# Z80fun_CPUtest.net
KiCad netlist of a schematic drawn in EAGLE
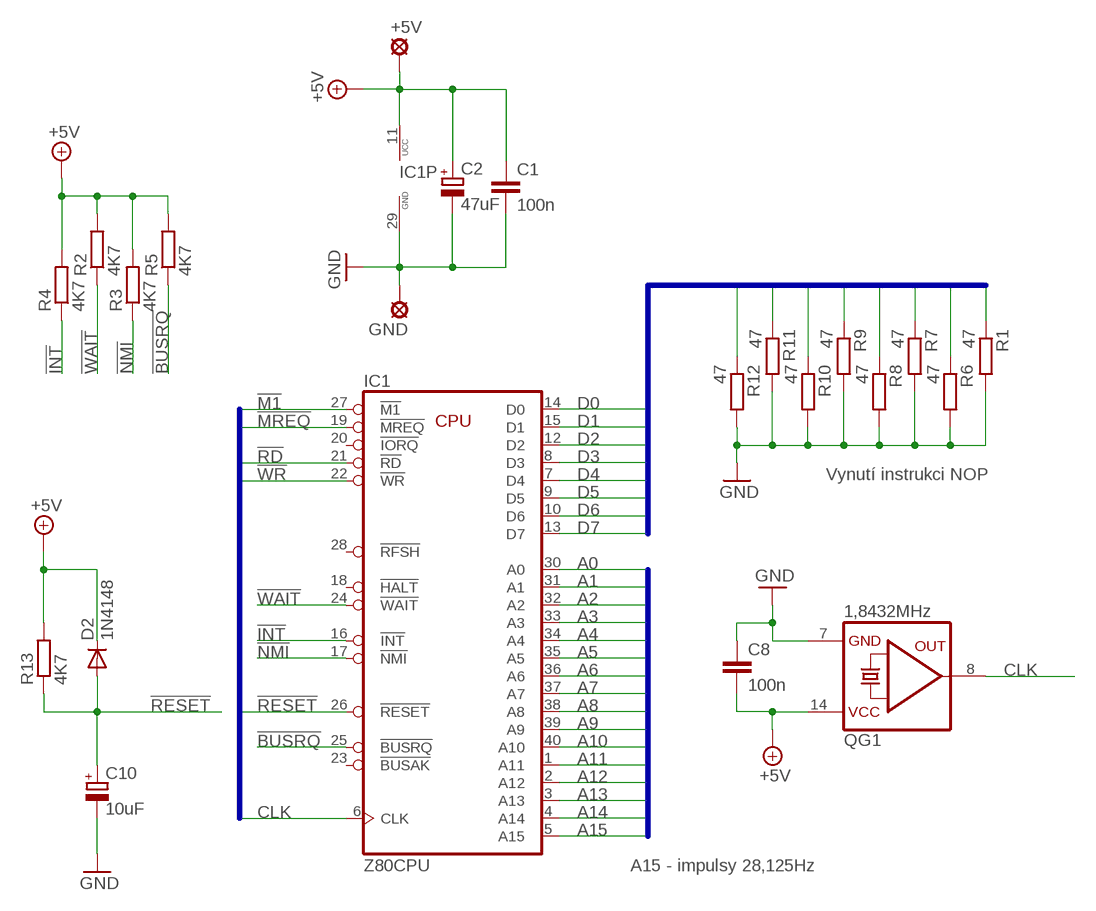
[diagram p0: schematic, sheet 1]

(export (version "E")
  (design (tool "Eeschema 10.0.6"))
  (components
    (comp (ref "+5V")
      (value "LSP11")
      (footprint "eagle-import:LSP11")
      (libsource (lib "eagle-import") (part "LSP11"))
    )
    (comp (ref "C1")
      (value "100n")
      (footprint "eagle-import:C050-024X044")
      (libsource (lib "eagle-import") (part "C-EU050-024X044"))
    )
    (comp (ref "C2")
      (value "47uF")
      (footprint "eagle-import:E2,5-6E")
      (libsource (lib "eagle-import") (part "CPOL-EUE2,5-6E"))
    )
    (comp (ref "C8")
      (value "100n")
      (footprint "eagle-import:C050-024X044")
      (libsource (lib "eagle-import") (part "C-EU050-024X044"))
    )
    (comp (ref "C10")
      (value "10uF")
      (footprint "eagle-import:E2,5-5")
      (libsource (lib "eagle-import") (part "CPOL-EUE2.5-5"))
    )
    (comp (ref "D2")
      (value "1N4148")
      (footprint "eagle-import:DO35-7")
      (libsource (lib "eagle-import") (part "1N4148DO35-7"))
    )
    (comp (ref "GND")
      (value "LSP11")
      (footprint "eagle-import:LSP11")
      (libsource (lib "eagle-import") (part "LSP11"))
    )
    (comp (ref "IC1")
      (value "Z80CPU")
      (footprint "eagle-import:DIL40")
      (libsource (lib "eagle-import") (part "Z80CPU"))
    )
    (comp (ref "QG1")
      (value "1,8432MHz")
      (footprint "eagle-import:DIL14S")
      (libsource (lib "eagle-import") (part "QG5860"))
    )
    (comp (ref "R1")
      (value "47")
      (footprint "eagle-import:0207_12")
      (libsource (lib "eagle-import") (part "R-EU_0207/12"))
    )
    (comp (ref "R2")
      (value "4K7")
      (footprint "eagle-import:0207_10")
      (libsource (lib "eagle-import") (part "R-EU_0207/10"))
    )
    (comp (ref "R3")
      (value "4K7")
      (footprint "eagle-import:0207_10")
      (libsource (lib "eagle-import") (part "R-EU_0207/10"))
    )
    (comp (ref "R4")
      (value "4K7")
      (footprint "eagle-import:0207_12")
      (libsource (lib "eagle-import") (part "R-EU_0207/12"))
    )
    (comp (ref "R5")
      (value "4K7")
      (footprint "eagle-import:0207_12")
      (libsource (lib "eagle-import") (part "R-EU_0207/12"))
    )
    (comp (ref "R6")
      (value "47")
      (footprint "eagle-import:0207_12")
      (libsource (lib "eagle-import") (part "R-EU_0207/12"))
    )
    (comp (ref "R7")
      (value "47")
      (footprint "eagle-import:0207_12")
      (libsource (lib "eagle-import") (part "R-EU_0207/12"))
    )
    (comp (ref "R8")
      (value "47")
      (footprint "eagle-import:0207_12")
      (libsource (lib "eagle-import") (part "R-EU_0207/12"))
    )
    (comp (ref "R9")
      (value "47")
      (footprint "eagle-import:0207_12")
      (libsource (lib "eagle-import") (part "R-EU_0207/12"))
    )
    (comp (ref "R10")
      (value "47")
      (footprint "eagle-import:0207_12")
      (libsource (lib "eagle-import") (part "R-EU_0207/12"))
    )
    (comp (ref "R11")
      (value "47")
      (footprint "eagle-import:0207_12")
      (libsource (lib "eagle-import") (part "R-EU_0207/12"))
    )
    (comp (ref "R12")
      (value "47")
      (footprint "eagle-import:0207_12")
      (libsource (lib "eagle-import") (part "R-EU_0207/12"))
    )
    (comp (ref "R13")
      (value "4K7")
      (footprint "eagle-import:0207_10")
      (libsource (lib "eagle-import") (part "R-EU_0207/10"))
    )
  )
  (nets
    (net (code "1") (name "+5V") (class "Default")
      (node (ref "+5V") (pin "MP") (pinfunction "MP_MP") (pintype "passive"))
      (node (ref "C1") (pin "1") (pinfunction "1_1") (pintype "passive"))
      (node (ref "C2") (pin "+") (pinfunction "+_+") (pintype "passive"))
      (node (ref "C8") (pin "2") (pinfunction "2_2") (pintype "passive"))
      (node (ref "D2") (pin "C") (pinfunction "C_C") (pintype "passive"))
      (node (ref "IC1") (pin "11") (pinfunction "UCC_11") (pintype "power_in"))
      (node (ref "QG1") (pin "14") (pinfunction "VCC_14") (pintype "power_in"))
      (node (ref "R13") (pin "2") (pinfunction "2_2") (pintype "passive"))
      (node (ref "R2") (pin "2") (pinfunction "2_2") (pintype "passive"))
      (node (ref "R3") (pin "2") (pinfunction "2_2") (pintype "passive"))
      (node (ref "R4") (pin "2") (pinfunction "2_2") (pintype "passive"))
      (node (ref "R5") (pin "2") (pinfunction "2_2") (pintype "passive"))
    )
    (net (code "2") (name "/A0") (class "Default")
      (node (ref "IC1") (pin "30") (pinfunction "A0_30") (pintype "output"))
    )
    (net (code "3") (name "/A1") (class "Default")
      (node (ref "IC1") (pin "31") (pinfunction "A1_31") (pintype "output"))
    )
    (net (code "4") (name "/A2") (class "Default")
      (node (ref "IC1") (pin "32") (pinfunction "A2_32") (pintype "output"))
    )
    (net (code "5") (name "/A3") (class "Default")
      (node (ref "IC1") (pin "33") (pinfunction "A3_33") (pintype "output"))
    )
    (net (code "6") (name "/A4") (class "Default")
      (node (ref "IC1") (pin "34") (pinfunction "A4_34") (pintype "output"))
    )
    (net (code "7") (name "/A5") (class "Default")
      (node (ref "IC1") (pin "35") (pinfunction "A5_35") (pintype "output"))
    )
    (net (code "8") (name "/A6") (class "Default")
      (node (ref "IC1") (pin "36") (pinfunction "A6_36") (pintype "output"))
    )
    (net (code "9") (name "/A7") (class "Default")
      (node (ref "IC1") (pin "37") (pinfunction "A7_37") (pintype "output"))
    )
    (net (code "10") (name "/A8") (class "Default")
      (node (ref "IC1") (pin "38") (pinfunction "A8_38") (pintype "output"))
    )
    (net (code "11") (name "/A9") (class "Default")
      (node (ref "IC1") (pin "39") (pinfunction "A9_39") (pintype "output"))
    )
    (net (code "12") (name "/A10") (class "Default")
      (node (ref "IC1") (pin "40") (pinfunction "A10_40") (pintype "output"))
    )
    (net (code "13") (name "/A11") (class "Default")
      (node (ref "IC1") (pin "1") (pinfunction "A11_1") (pintype "output"))
    )
    (net (code "14") (name "/A12") (class "Default")
      (node (ref "IC1") (pin "2") (pinfunction "A12_2") (pintype "output"))
    )
    (net (code "15") (name "/A13") (class "Default")
      (node (ref "IC1") (pin "3") (pinfunction "A13_3") (pintype "output"))
    )
    (net (code "16") (name "/A14") (class "Default")
      (node (ref "IC1") (pin "4") (pinfunction "A14_4") (pintype "output"))
    )
    (net (code "17") (name "/A15") (class "Default")
      (node (ref "IC1") (pin "5") (pinfunction "A15_5") (pintype "output"))
    )
    (net (code "18") (name "/CLK") (class "Default")
      (node (ref "IC1") (pin "6") (pinfunction "CLK_6") (pintype "input"))
      (node (ref "QG1") (pin "8") (pinfunction "OUT_8") (pintype "output"))
    )
    (net (code "19") (name "/D0") (class "Default")
      (node (ref "IC1") (pin "14") (pinfunction "D0_14") (pintype "bidirectional"))
      (node (ref "R1") (pin "1") (pinfunction "1_1") (pintype "passive"))
    )
    (net (code "20") (name "/D1") (class "Default")
      (node (ref "IC1") (pin "15") (pinfunction "D1_15") (pintype "bidirectional"))
      (node (ref "R6") (pin "1") (pinfunction "1_1") (pintype "passive"))
    )
    (net (code "21") (name "/D2") (class "Default")
      (node (ref "IC1") (pin "12") (pinfunction "D2_12") (pintype "bidirectional"))
      (node (ref "R7") (pin "1") (pinfunction "1_1") (pintype "passive"))
    )
    (net (code "22") (name "/D3") (class "Default")
      (node (ref "IC1") (pin "8") (pinfunction "D3_8") (pintype "bidirectional"))
      (node (ref "R8") (pin "1") (pinfunction "1_1") (pintype "passive"))
    )
    (net (code "23") (name "/D4") (class "Default")
      (node (ref "IC1") (pin "7") (pinfunction "D4_7") (pintype "bidirectional"))
      (node (ref "R9") (pin "1") (pinfunction "1_1") (pintype "passive"))
    )
    (net (code "24") (name "/D5") (class "Default")
      (node (ref "IC1") (pin "9") (pinfunction "D5_9") (pintype "bidirectional"))
      (node (ref "R10") (pin "1") (pinfunction "1_1") (pintype "passive"))
    )
    (net (code "25") (name "/D6") (class "Default")
      (node (ref "IC1") (pin "10") (pinfunction "D6_10") (pintype "bidirectional"))
      (node (ref "R11") (pin "1") (pinfunction "1_1") (pintype "passive"))
    )
    (net (code "26") (name "/D7") (class "Default")
      (node (ref "IC1") (pin "13") (pinfunction "D7_13") (pintype "bidirectional"))
      (node (ref "R12") (pin "1") (pinfunction "1_1") (pintype "passive"))
    )
    (net (code "27") (name "/~{BUSRQ}") (class "Default")
      (node (ref "IC1") (pin "25") (pinfunction "~{BUSRQ}_25") (pintype "input"))
      (node (ref "R5") (pin "1") (pinfunction "1_1") (pintype "passive"))
    )
    (net (code "28") (name "/~{INT}") (class "Default")
      (node (ref "IC1") (pin "16") (pinfunction "~{INT}_16") (pintype "input"))
      (node (ref "R4") (pin "1") (pinfunction "1_1") (pintype "passive"))
    )
    (net (code "29") (name "/~{M1}") (class "Default")
      (node (ref "IC1") (pin "27") (pinfunction "~{M1}_27") (pintype "output"))
    )
    (net (code "30") (name "/~{MREQ}") (class "Default")
      (node (ref "IC1") (pin "19") (pinfunction "~{MREQ}_19") (pintype "output"))
    )
    (net (code "31") (name "/~{NMI}") (class "Default")
      (node (ref "IC1") (pin "17") (pinfunction "~{NMI}_17") (pintype "input"))
      (node (ref "R3") (pin "1") (pinfunction "1_1") (pintype "passive"))
    )
    (net (code "32") (name "/~{RD}") (class "Default")
      (node (ref "IC1") (pin "21") (pinfunction "~{RD}_21") (pintype "output"))
    )
    (net (code "33") (name "/~{RESET}") (class "Default")
      (node (ref "C10") (pin "+") (pinfunction "+_+") (pintype "passive"))
      (node (ref "D2") (pin "A") (pinfunction "A_A") (pintype "passive"))
      (node (ref "IC1") (pin "26") (pinfunction "~{RESET}_26") (pintype "input"))
      (node (ref "R13") (pin "1") (pinfunction "1_1") (pintype "passive"))
    )
    (net (code "34") (name "/~{WAIT}") (class "Default")
      (node (ref "IC1") (pin "24") (pinfunction "~{WAIT}_24") (pintype "input"))
      (node (ref "R2") (pin "1") (pinfunction "1_1") (pintype "passive"))
    )
    (net (code "35") (name "/~{WR}") (class "Default")
      (node (ref "IC1") (pin "22") (pinfunction "~{WR}_22") (pintype "output"))
    )
    (net (code "36") (name "GND") (class "Default")
      (node (ref "C1") (pin "2") (pinfunction "2_2") (pintype "passive"))
      (node (ref "C10") (pin "-") (pinfunction "-_-") (pintype "passive"))
      (node (ref "C2") (pin "-") (pinfunction "-_-") (pintype "passive"))
      (node (ref "C8") (pin "1") (pinfunction "1_1") (pintype "passive"))
      (node (ref "GND") (pin "MP") (pinfunction "MP_MP") (pintype "passive"))
      (node (ref "IC1") (pin "29") (pinfunction "GND_29") (pintype "power_in"))
      (node (ref "QG1") (pin "7") (pinfunction "GND_7") (pintype "power_in"))
      (node (ref "R1") (pin "2") (pinfunction "2_2") (pintype "passive"))
      (node (ref "R10") (pin "2") (pinfunction "2_2") (pintype "passive"))
      (node (ref "R11") (pin "2") (pinfunction "2_2") (pintype "passive"))
      (node (ref "R12") (pin "2") (pinfunction "2_2") (pintype "passive"))
      (node (ref "R6") (pin "2") (pinfunction "2_2") (pintype "passive"))
      (node (ref "R7") (pin "2") (pinfunction "2_2") (pintype "passive"))
      (node (ref "R8") (pin "2") (pinfunction "2_2") (pintype "passive"))
      (node (ref "R9") (pin "2") (pinfunction "2_2") (pintype "passive"))
    )
    (net (code "37") (name "unconnected-(IC1A-~{BUSAK}-Pad23)") (class "Default")
      (node (ref "IC1") (pin "23") (pinfunction "~{BUSAK}_23") (pintype "output"))
    )
    (net (code "38") (name "unconnected-(IC1A-~{HALT}-Pad18)") (class "Default")
      (node (ref "IC1") (pin "18") (pinfunction "~{HALT}_18") (pintype "output"))
    )
    (net (code "39") (name "unconnected-(IC1A-~{IORQ}-Pad20)") (class "Default")
      (node (ref "IC1") (pin "20") (pinfunction "~{IORQ}_20") (pintype "output"))
    )
    (net (code "40") (name "unconnected-(IC1A-~{RFSH}-Pad28)") (class "Default")
      (node (ref "IC1") (pin "28") (pinfunction "~{RFSH}_28") (pintype "output"))
    )
  )
)
